# Airbeamv0_01-rn4020.net
KiCad netlist of a schematic drawn in EAGLE
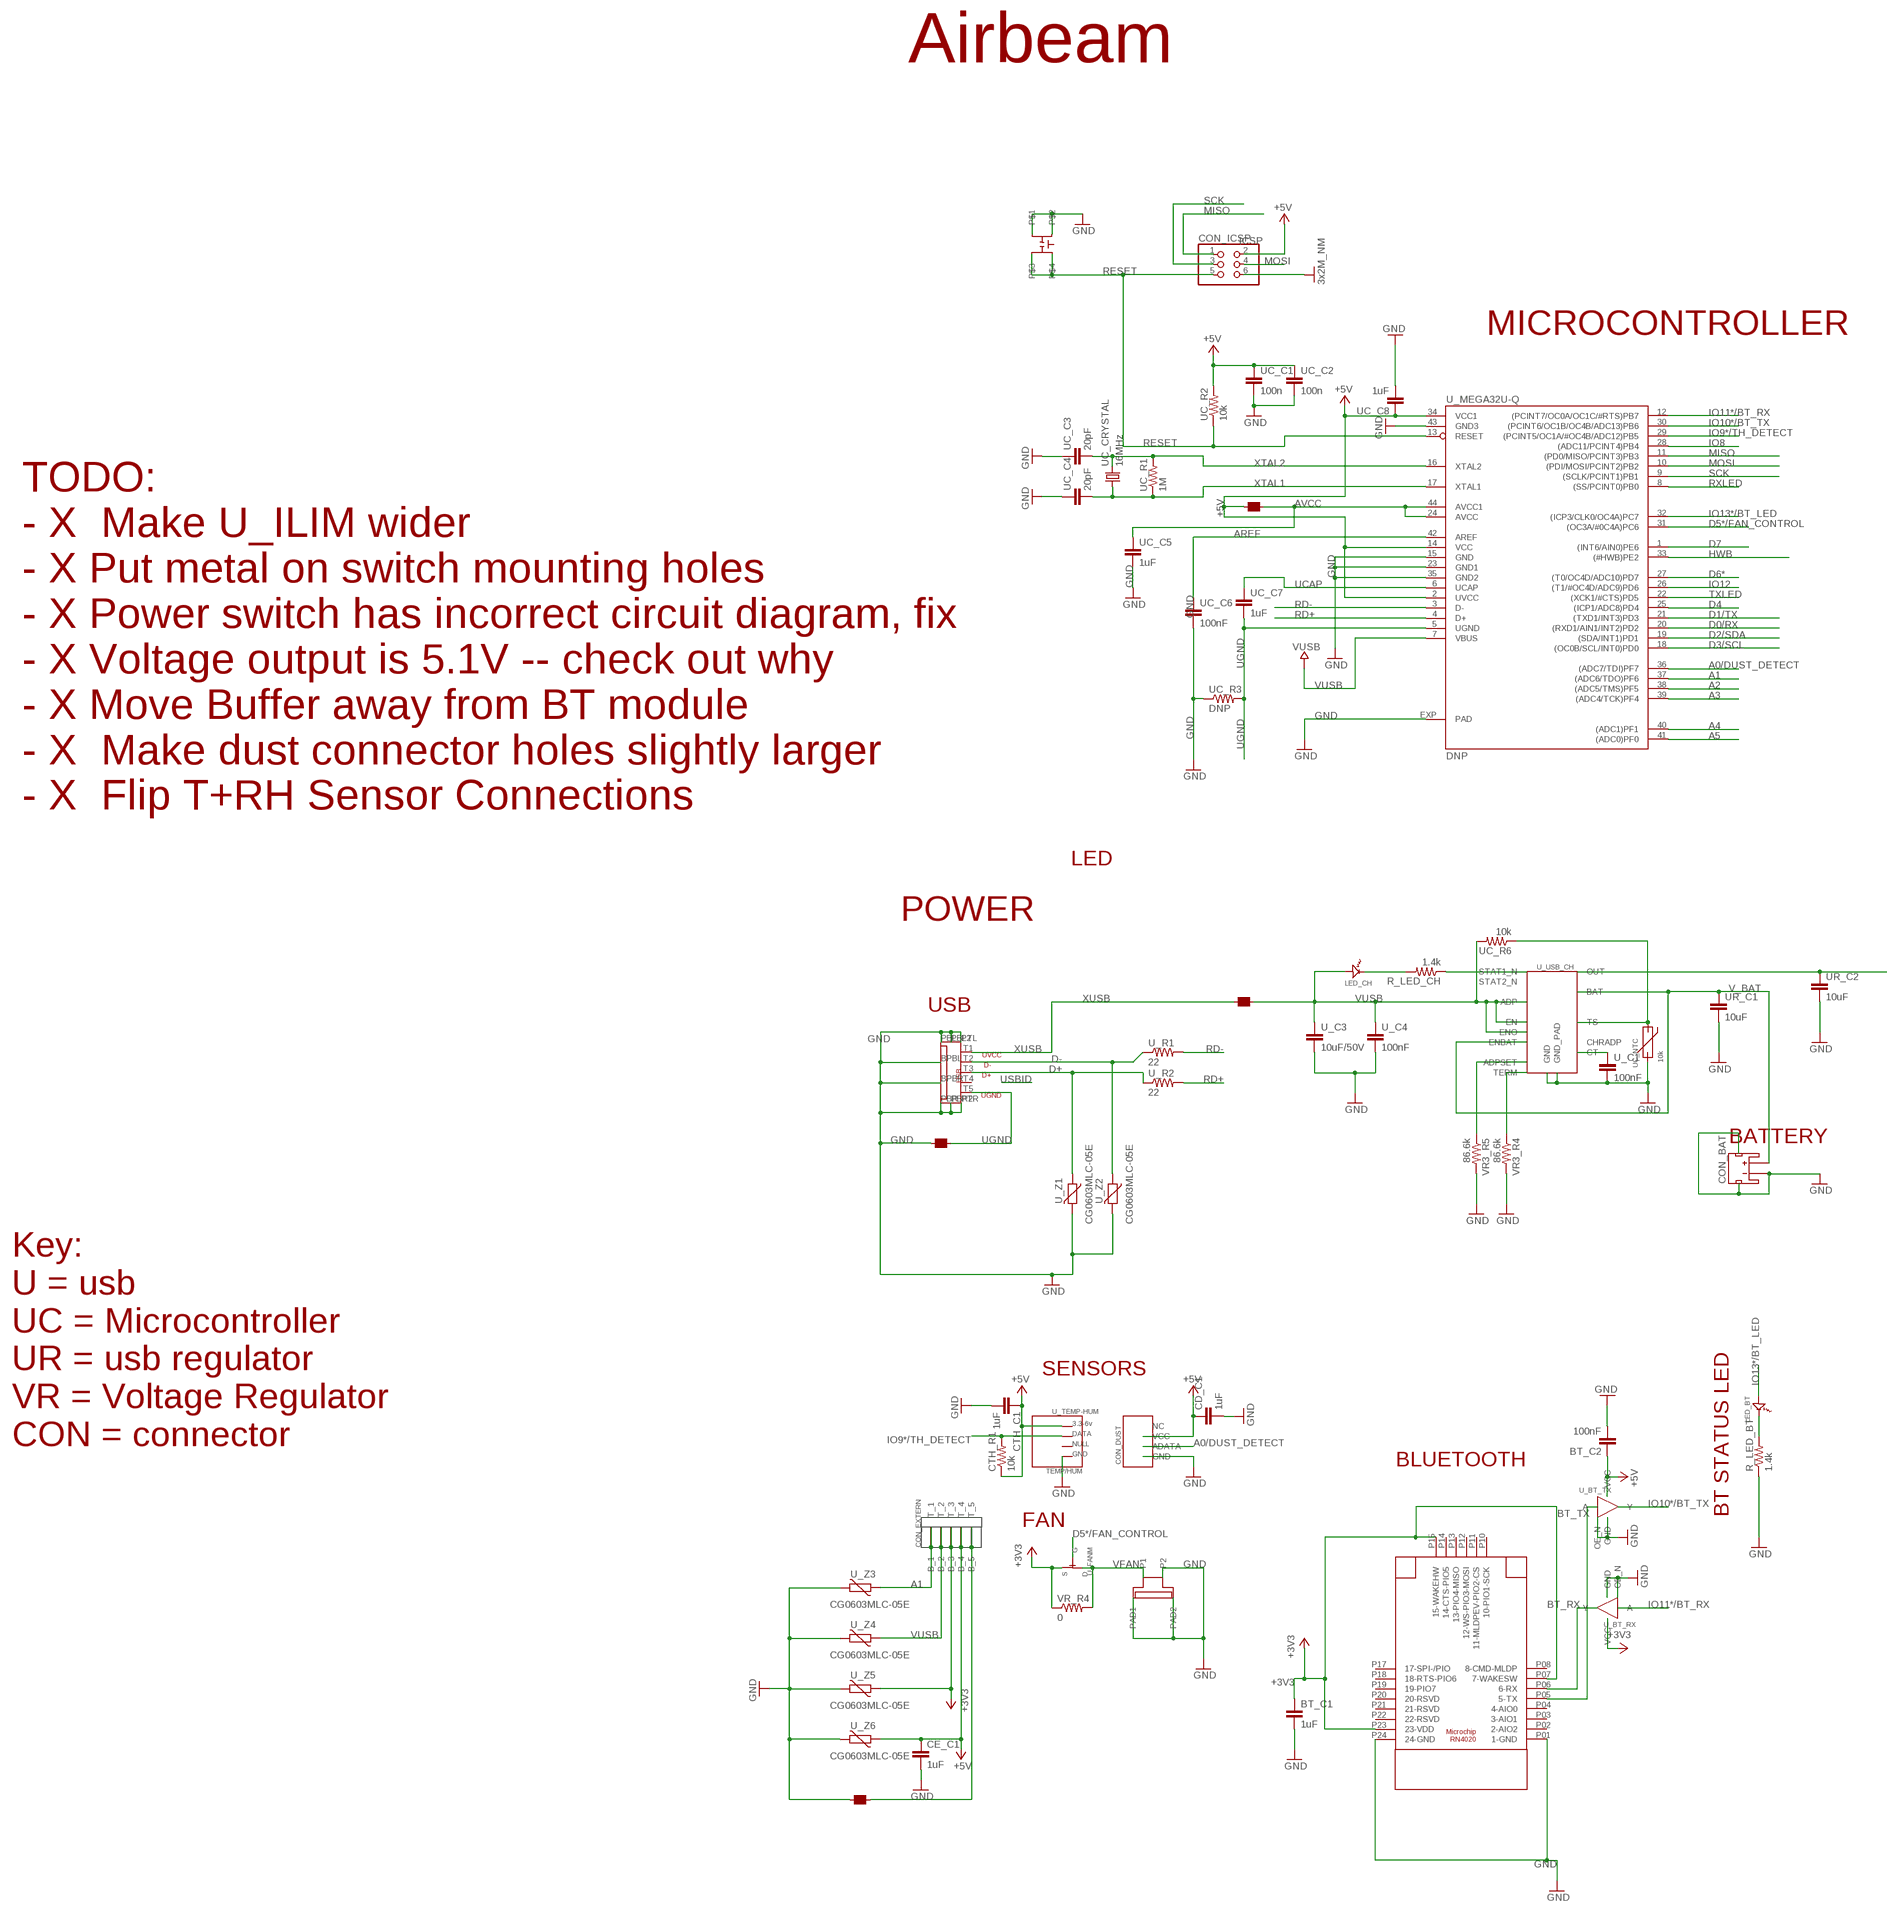
[diagram p0: schematic, sheet 1, part 1 of 2]
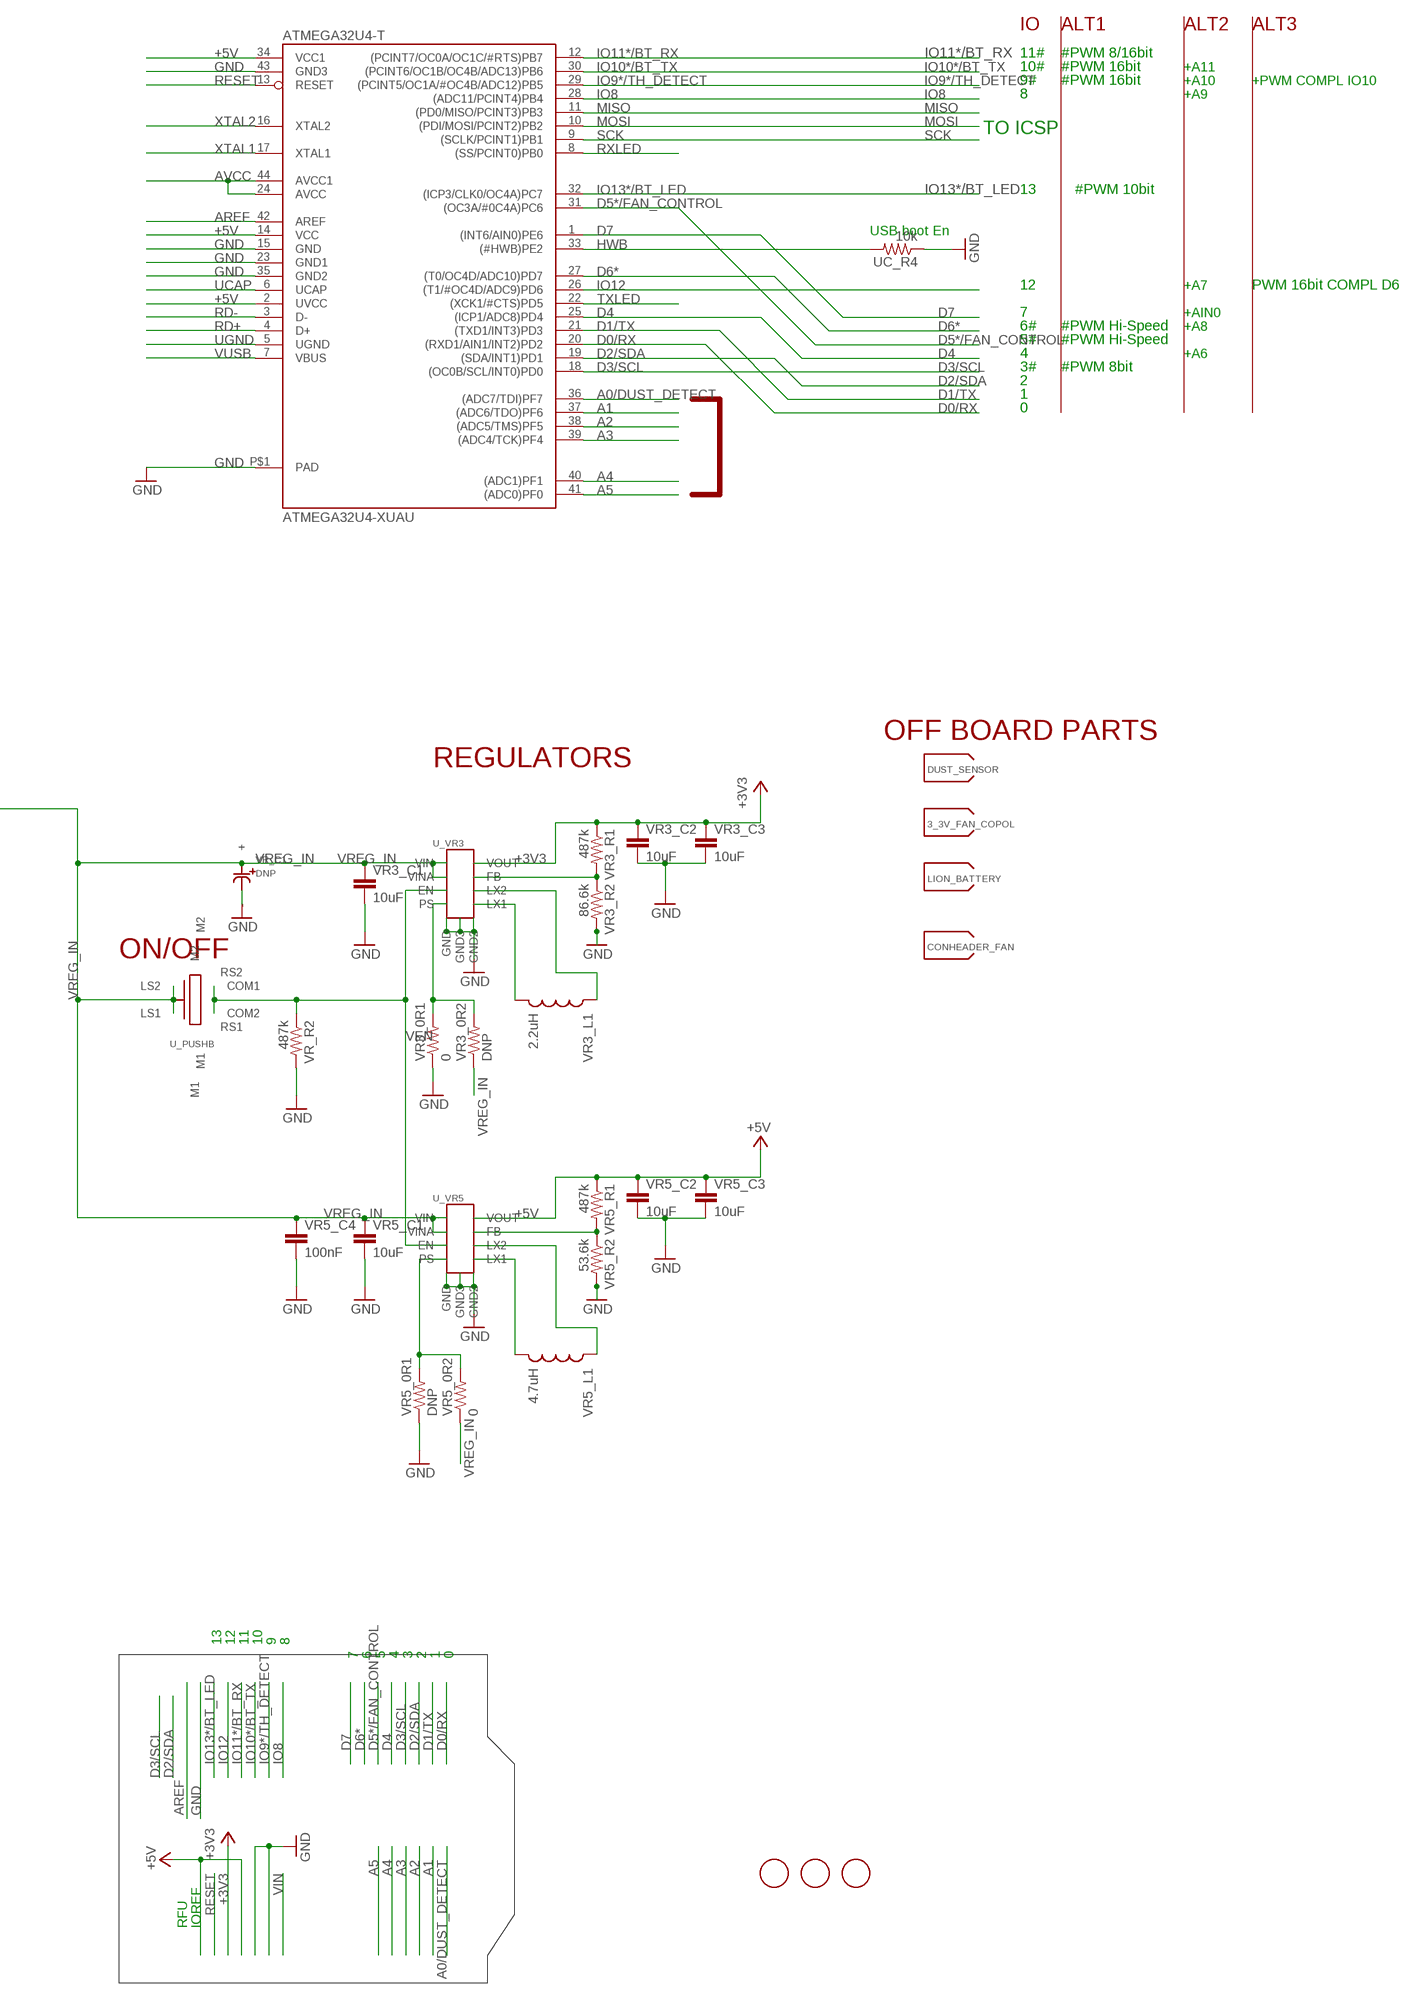
[diagram p1: schematic, sheet 1, part 2 of 2]

(export (version "E")
  (design (tool "Eeschema 10.0.6"))
  (components
    (comp (ref "3_3V_FAN_COPOL")
      (value "OFF_BOARD")
      (footprint "eagle-import:EMPTY")
      (fields (field (name "PARTNO") "F16FB-05LLC/E"))
      (libsource (lib "eagle-import") (part "PART_OFFBOARD"))
    )
    (comp (ref "ATMEGA32U4-T")
      (value "ATMEGA32U4-XUAU")
      (footprint "eagle-import:TQFP44-PAD")
      (fields (field (name "PARTNO") "ATMEGA32U4-AU"))
      (libsource (lib "eagle-import") (part "ATMEGA32U4-XUAU"))
    )
    (comp (ref "BT_C1")
      (value "1uF")
      (footprint "eagle-import:0603-CAP")
      (fields (field (name "PARTNO") "C1608X5R1C105K080AA"))
      (libsource (lib "eagle-import") (part "CAP0603-CAP"))
    )
    (comp (ref "BT_C2")
      (value "100nF")
      (footprint "eagle-import:0603-CAP")
      (fields (field (name "PARTNO") "C1608X7R1E104K080AA"))
      (libsource (lib "eagle-import") (part "CAP0603-CAP"))
    )
    (comp (ref "CA_FB1")
      (value "FERITE_BEAD")
      (footprint "eagle-import:U_FB1")
      (fields (field (name "PARTNO") "MH2029-600Y"))
      (libsource (lib "eagle-import") (part "FERITE_BEAD"))
    )
    (comp (ref "CD_C1")
      (value "1uF")
      (footprint "eagle-import:0603-CAP")
      (fields (field (name "PARTNO") "C1608X5R1C105K080AA"))
      (libsource (lib "eagle-import") (part "CAP0603-CAP"))
    )
    (comp (ref "CE_C1")
      (value "1uF")
      (footprint "eagle-import:0603-CAP")
      (fields (field (name "PARTNO") "C1608X5R1C105K080AA"))
      (libsource (lib "eagle-import") (part "CAP0603-CAP"))
    )
    (comp (ref "CONHEADER_FAN")
      (value "OFF_BOARD")
      (footprint "eagle-import:EMPTY")
      (fields (field (name "PARTNO") "02SUR-32S"))
      (libsource (lib "eagle-import") (part "PART_OFFBOARD"))
    )
    (comp (ref "CON_BAT")
      (value "CON_BAT")
      (footprint "eagle-import:JST-2-SMD")
      (fields (field (name "PARTNO") "S2B-PH-SM4-TB(LF)(SN)"))
      (libsource (lib "eagle-import") (part "JST_2MM_MALE"))
    )
    (comp (ref "CON_DUST")
      (value "CON_DUST")
      (footprint "eagle-import:S4B-EH")
      (fields (field (name "PARTNO") "S4B-EH"))
      (libsource (lib "eagle-import") (part "CON_DUST"))
    )
    (comp (ref "CON_EXTERN")
      (value "TBLOCK_5")
      (footprint "eagle-import:TBLOCK_5")
      (fields (field (name "PARTNO") "1770911"))
      (libsource (lib "eagle-import") (part "TBLOCK_5"))
    )
    (comp (ref "CON_FAN")
      (value "SUR_2PIN")
      (footprint "eagle-import:JST-0.8MM")
      (fields (field (name "PARTNO") "SM02B-SURS-TF"))
      (libsource (lib "eagle-import") (part "SUR_2PIN"))
    )
    (comp (ref "CON_ICSP")
      (value "ICSP")
      (footprint "eagle-import:2X03")
      (fields (field (name "PARTNO") "67997-206HLF "))
      (libsource (lib "eagle-import") (part "PINHD-2X3"))
    )
    (comp (ref "CON_USB")
      (value "USB-FCI")
      (footprint "eagle-import:USB-FCI")
      (fields (field (name "PARTNO") "10103594-0001LF"))
      (libsource (lib "eagle-import") (part "USB-FCI"))
    )
    (comp (ref "CTH_C1")
      (value "1uF")
      (footprint "eagle-import:0603-CAP")
      (fields (field (name "PARTNO") "C1608X5R1C105K080AA"))
      (libsource (lib "eagle-import") (part "CAP0603-CAP"))
    )
    (comp (ref "CTH_R1")
      (value "10k")
      (footprint "eagle-import:0603-RES")
      (fields (field (name "PARTNO") "RC0603JR-0710KL"))
      (libsource (lib "eagle-import") (part "RESISTOR0603-RES"))
    )
    (comp (ref "DUST_SENSOR")
      (value "OFF_BOARD")
      (footprint "eagle-import:EMPTY")
      (fields (field (name "PARTNO") "PPD60PV-T2"))
      (libsource (lib "eagle-import") (part "PART_OFFBOARD"))
    )
    (comp (ref "FID1")
      (value "FIDUCIALMOUNT")
      (footprint "eagle-import:FIDUCIA-MOUNT")
      (fields (field (name "PARTNO") "DNP"))
      (libsource (lib "eagle-import") (part "FIDUCIALMOUNT"))
    )
    (comp (ref "FID2")
      (value "FIDUCIALMOUNT")
      (footprint "eagle-import:FIDUCIA-MOUNT")
      (fields (field (name "PARTNO") "DNP"))
      (libsource (lib "eagle-import") (part "FIDUCIALMOUNT"))
    )
    (comp (ref "FID3")
      (value "FIDUCIALMOUNT")
      (footprint "eagle-import:FIDUCIA-MOUNT")
      (fields (field (name "PARTNO") "DNP"))
      (libsource (lib "eagle-import") (part "FIDUCIALMOUNT"))
    )
    (comp (ref "LED_BT")
      (value "LED")
      (footprint "eagle-import:LED_550")
      (fields (field (name "PARTNO") "550-1107F "))
      (libsource (lib "eagle-import") (part "LED"))
    )
    (comp (ref "LED_CH")
      (value "LED")
      (footprint "eagle-import:LED_550")
      (fields (field (name "PARTNO") "550-1307F"))
      (libsource (lib "eagle-import") (part "LED"))
    )
    (comp (ref "LION_BATTERY")
      (value "OFF_BOARD")
      (footprint "eagle-import:EMPTY")
      (fields (field (name "PARTNO") "585460_2000mAh"))
      (libsource (lib "eagle-import") (part "PART_OFFBOARD"))
    )
    (comp (ref "RESET_SWITCH")
      (value "DNP")
      (footprint "eagle-import:SWITCH_TACTILE")
      (fields (field (name "PARTNO") "TL3315NF250Q"))
      (libsource (lib "eagle-import") (part "SWITCH"))
    )
    (comp (ref "R_LED_BT")
      (value "1.4k")
      (footprint "eagle-import:0603-RES")
      (fields (field (name "PARTNO") "RC0603FR-071K4L"))
      (libsource (lib "eagle-import") (part "RESISTOR0603-RES"))
    )
    (comp (ref "R_LED_CH")
      (value "1.4k")
      (footprint "eagle-import:0603-RES")
      (fields (field (name "PARTNO") "RC0603FR-071K4L"))
      (libsource (lib "eagle-import") (part "RESISTOR0603-RES"))
    )
    (comp (ref "U$1")
      (value "RN4020")
      (footprint "eagle-import:RN4020SMD")
      (libsource (lib "eagle-import") (part "RN4020"))
    )
    (comp (ref "UC_C1")
      (value "100n")
      (footprint "eagle-import:0603-CAP")
      (fields (field (name "PARTNO") "C1608X7R1E104K080AA"))
      (libsource (lib "eagle-import") (part "CAP0603-CAP"))
    )
    (comp (ref "UC_C2")
      (value "100n")
      (footprint "eagle-import:0603-CAP")
      (fields (field (name "PARTNO") "C1608X7R1E104K080AA"))
      (libsource (lib "eagle-import") (part "CAP0603-CAP"))
    )
    (comp (ref "UC_C3")
      (value "20pF")
      (footprint "eagle-import:0603-CAP")
      (fields (field (name "PARTNO") "CL10C200JB8NNNC"))
      (libsource (lib "eagle-import") (part "CAP0603-CAP"))
    )
    (comp (ref "UC_C4")
      (value "20pF")
      (footprint "eagle-import:0603-CAP")
      (fields (field (name "PARTNO") "CL10C200JB8NNNC"))
      (libsource (lib "eagle-import") (part "CAP0603-CAP"))
    )
    (comp (ref "UC_C5")
      (value "1uF")
      (footprint "eagle-import:0603-CAP")
      (fields (field (name "PARTNO") "C1608X5R1C105K080AA"))
      (libsource (lib "eagle-import") (part "CAP0603-CAP"))
    )
    (comp (ref "UC_C6")
      (value "100nF")
      (footprint "eagle-import:0603-CAP")
      (fields (field (name "PARTNO") "C1608X7R1E104K080AA"))
      (libsource (lib "eagle-import") (part "CAP0603-CAP"))
    )
    (comp (ref "UC_C7")
      (value "1uF")
      (footprint "eagle-import:0603-CAP")
      (fields (field (name "PARTNO") "C1608X5R1C105K080AA"))
      (libsource (lib "eagle-import") (part "CAP0603-CAP"))
    )
    (comp (ref "UC_C8")
      (value "1uF")
      (footprint "eagle-import:0603-CAP")
      (fields (field (name "PARTNO") "C1608X5R1C105K080AA"))
      (libsource (lib "eagle-import") (part "CAP0603-CAP"))
    )
    (comp (ref "UC_CRYSTAL")
      (value "16MHz")
      (footprint "eagle-import:HC49UP")
      (fields (field (name "PARTNO") "ECS-160-20-3X-TR "))
      (libsource (lib "eagle-import") (part "CRYSTALSMD"))
    )
    (comp (ref "UC_NTC")
      (value "10k")
      (footprint "eagle-import:0402")
      (fields (field (name "PARTNO") "ERT-J0EM103J ") (field (name "PARTNO_1") "ERT-J0EM103J"))
      (libsource (lib "eagle-import") (part "THERMISTOR0402"))
    )
    (comp (ref "UC_R1")
      (value "1M")
      (footprint "eagle-import:0603-RES")
      (fields (field (name "PARTNO") "RC0603FR-071ML"))
      (libsource (lib "eagle-import") (part "RESISTOR0603-RES"))
    )
    (comp (ref "UC_R2")
      (value "10k")
      (footprint "eagle-import:0603-RES")
      (fields (field (name "PARTNO") "RC0603JR-0710KL"))
      (libsource (lib "eagle-import") (part "RESISTOR0603-RES"))
    )
    (comp (ref "UC_R3")
      (value "DNP")
      (footprint "eagle-import:0603-RES")
      (fields (field (name "PARTNO") "RC0603JR-070RL"))
      (libsource (lib "eagle-import") (part "RESISTOR0603-RES"))
    )
    (comp (ref "UC_R4")
      (value "10k")
      (footprint "eagle-import:0603-RES")
      (fields (field (name "PARTNO") "RC0603JR-0710KL"))
      (libsource (lib "eagle-import") (part "RESISTOR0603-RES"))
    )
    (comp (ref "UC_R6")
      (value "10k")
      (footprint "eagle-import:0603-RES")
      (fields (field (name "PARTNO") "RC0603JR-0710KL"))
      (libsource (lib "eagle-import") (part "RESISTOR0603-RES"))
    )
    (comp (ref "UR_C1")
      (value "10uF")
      (footprint "eagle-import:0805")
      (fields (field (name "PARTNO") "C2012X5R1C106K085AC"))
      (libsource (lib "eagle-import") (part "CAP0805"))
    )
    (comp (ref "UR_C2")
      (value "10uF")
      (footprint "eagle-import:0805")
      (fields (field (name "PARTNO") "C2012X5R1C106K085AC"))
      (libsource (lib "eagle-import") (part "CAP0805"))
    )
    (comp (ref "U_BT_RX")
      (value "V_BUFFER")
      (footprint "eagle-import:SOT23-5")
      (fields (field (name "PARTNO") "SN74LVC1G125DBVR"))
      (libsource (lib "eagle-import") (part "V_BUFFER"))
    )
    (comp (ref "U_BT_TX")
      (value "V_BUFFER")
      (footprint "eagle-import:SOT23-5")
      (fields (field (name "PARTNO") "SN74LVC1G125DBVR"))
      (libsource (lib "eagle-import") (part "V_BUFFER"))
    )
    (comp (ref "U_C1")
      (value "100nF")
      (footprint "eagle-import:0603-CAP")
      (fields (field (name "PARTNO") "C1608X7R1E104K080AA"))
      (libsource (lib "eagle-import") (part "CAP0603-CAP"))
    )
    (comp (ref "U_C3")
      (value "10uF/50V")
      (footprint "eagle-import:1206")
      (fields (field (name "PARTNO") "CL31A106KBHNNNE "))
      (libsource (lib "eagle-import") (part "CAP1206"))
    )
    (comp (ref "U_C4")
      (value "100nF")
      (footprint "eagle-import:0603-CAP")
      (fields (field (name "PARTNO") "CC0603ZRY5V9BB104"))
      (libsource (lib "eagle-import") (part "CAP0603-CAP"))
    )
    (comp (ref "U_FANM")
      (value "DNP")
      (footprint "eagle-import:SOT23")
      (fields (field (name "PARTNO") "NDS331N"))
      (libsource (lib "eagle-import") (part "MOSFET-N"))
    )
    (comp (ref "U_FB1")
      (value "FERITE_BEAD")
      (footprint "eagle-import:U_FB1")
      (fields (field (name "PARTNO") "MH2029-600Y"))
      (libsource (lib "eagle-import") (part "FERITE_BEAD"))
    )
    (comp (ref "U_FB2")
      (value "FERITE_BEAD")
      (footprint "eagle-import:U_FB1")
      (fields (field (name "PARTNO") "MH2029-600Y"))
      (libsource (lib "eagle-import") (part "FERITE_BEAD"))
    )
    (comp (ref "U_FB3")
      (value "FERITE_BEAD")
      (footprint "eagle-import:U_FB1")
      (fields (field (name "PARTNO") "MH2029-600Y"))
      (libsource (lib "eagle-import") (part "FERITE_BEAD"))
    )
    (comp (ref "U_MEGA32U-Q")
      (value "DNP")
      (footprint "eagle-import:QFN44ML7X7")
      (fields (field (name "PARTNO") "ATMEGA32U4-MU "))
      (libsource (lib "eagle-import") (part "ATMEGA32U4-XUMU"))
    )
    (comp (ref "U_PUSHB")
      (value "PUSHBUTTON")
      (footprint "eagle-import:PUSHBUTTON")
      (fields (field (name "PARTNO") "LC2259EENP"))
      (libsource (lib "eagle-import") (part "PUSHBUTTON"))
    )
    (comp (ref "U_R1")
      (value "22")
      (footprint "eagle-import:0603-RES")
      (fields (field (name "PARTNO") "RC0603JR-0722RL"))
      (libsource (lib "eagle-import") (part "RESISTOR0603-RES"))
    )
    (comp (ref "U_R2")
      (value "22")
      (footprint "eagle-import:0603-RES")
      (fields (field (name "PARTNO") "RC0603JR-0722RL"))
      (libsource (lib "eagle-import") (part "RESISTOR0603-RES"))
    )
    (comp (ref "U_TEMP-HUM")
      (value "RHT03")
      (footprint "eagle-import:RHT03")
      (fields (field (name "PARTNO") "RHT03 "))
      (libsource (lib "eagle-import") (part "RHT03"))
    )
    (comp (ref "U_USB_CH")
      (value "USB-BATTERY_LOAD")
      (footprint "eagle-import:TDFN33-14")
      (fields (field (name "PARTNO") "AAT3672IWO-4.2-1-T1") (field (name "PARTNO_1") "AAT3672IWO-4.2-1-T1"))
      (libsource (lib "eagle-import") (part "USB-BATTERY_LOAD"))
    )
    (comp (ref "U_VR3")
      (value "VREG-RTEC6150")
      (footprint "eagle-import:WFDFN-10")
      (fields (field (name "PARTNO") "RT6150BGQW"))
      (libsource (lib "eagle-import") (part "VREG-RTEC6150"))
    )
    (comp (ref "U_VR5")
      (value "VREG-RTEC6150")
      (footprint "eagle-import:WFDFN-10")
      (fields (field (name "PARTNO") "RT6150BGQW"))
      (libsource (lib "eagle-import") (part "VREG-RTEC6150"))
    )
    (comp (ref "U_Z1")
      (value "CG0603MLC-05E")
      (footprint "eagle-import:CT_CN0603")
      (libsource (lib "eagle-import") (part "VARISTORCN0603"))
    )
    (comp (ref "U_Z2")
      (value "CG0603MLC-05E")
      (footprint "eagle-import:CT_CN0603")
      (libsource (lib "eagle-import") (part "VARISTORCN0603"))
    )
    (comp (ref "U_Z3")
      (value "CG0603MLC-05E")
      (footprint "eagle-import:CT_CN0603")
      (libsource (lib "eagle-import") (part "VARISTORCN0603"))
    )
    (comp (ref "U_Z4")
      (value "CG0603MLC-05E")
      (footprint "eagle-import:CT_CN0603")
      (libsource (lib "eagle-import") (part "VARISTORCN0603"))
    )
    (comp (ref "U_Z5")
      (value "CG0603MLC-05E")
      (footprint "eagle-import:CT_CN0603")
      (libsource (lib "eagle-import") (part "VARISTORCN0603"))
    )
    (comp (ref "U_Z6")
      (value "CG0603MLC-05E")
      (footprint "eagle-import:CT_CN0603")
      (libsource (lib "eagle-import") (part "VARISTORCN0603"))
    )
    (comp (ref "VR3_0R1")
      (value "0")
      (footprint "eagle-import:0603-RES")
      (fields (field (name "PARTNO") "RC0603JR-070RL"))
      (libsource (lib "eagle-import") (part "RESISTOR0603-RES"))
    )
    (comp (ref "VR3_0R2")
      (value "DNP")
      (footprint "eagle-import:0603-RES")
      (fields (field (name "PARTNO") "RC0603JR-070RL"))
      (libsource (lib "eagle-import") (part "RESISTOR0603-RES"))
    )
    (comp (ref "VR3_C1")
      (value "10uF")
      (footprint "eagle-import:0805")
      (fields (field (name "PARTNO") "C2012X5R1C106K085AC"))
      (libsource (lib "eagle-import") (part "CAP0805"))
    )
    (comp (ref "VR3_C2")
      (value "10uF")
      (footprint "eagle-import:0805")
      (fields (field (name "PARTNO") "C2012X5R1C106K085AC"))
      (libsource (lib "eagle-import") (part "CAP0805"))
    )
    (comp (ref "VR3_C3")
      (value "10uF")
      (footprint "eagle-import:0805")
      (fields (field (name "PARTNO") "C2012X5R1C106K085AC"))
      (libsource (lib "eagle-import") (part "CAP0805"))
    )
    (comp (ref "VR3_L1")
      (value "2.2uH")
      (footprint "eagle-import:1210")
      (fields (field (name "PARTNO") "BRL3225T2R2M"))
      (libsource (lib "eagle-import") (part "INDUCTOR1210"))
    )
    (comp (ref "VR3_R1")
      (value "487k")
      (footprint "eagle-import:0603-RES")
      (fields (field (name "PARTNO") "ERJ-3EKF4873V"))
      (libsource (lib "eagle-import") (part "RESISTOR0603"))
    )
    (comp (ref "VR3_R2")
      (value "86.6k")
      (footprint "eagle-import:0603-RES")
      (fields (field (name "PARTNO") "ERJ-3EKF8662V"))
      (libsource (lib "eagle-import") (part "RESISTOR0603"))
    )
    (comp (ref "VR3_R4")
      (value "86.6k")
      (footprint "eagle-import:0603-RES")
      (fields (field (name "PARTNO") "ERJ-3EKF8662V"))
      (libsource (lib "eagle-import") (part "RESISTOR0603"))
    )
    (comp (ref "VR3_R5")
      (value "86.6k")
      (footprint "eagle-import:0603-RES")
      (fields (field (name "PARTNO") "ERJ-3EKF8662V"))
      (libsource (lib "eagle-import") (part "RESISTOR0603"))
    )
    (comp (ref "VR5_0R1")
      (value "DNP")
      (footprint "eagle-import:0603-RES")
      (fields (field (name "PARTNO") "RC0603JR-070RL"))
      (libsource (lib "eagle-import") (part "RESISTOR0603-RES"))
    )
    (comp (ref "VR5_0R2")
      (value "0")
      (footprint "eagle-import:0603-RES")
      (fields (field (name "PARTNO") "RC0603JR-070RL"))
      (libsource (lib "eagle-import") (part "RESISTOR0603-RES"))
    )
    (comp (ref "VR5_C1")
      (value "10uF")
      (footprint "eagle-import:0805")
      (fields (field (name "PARTNO") "C2012X5R1C106K085AC"))
      (libsource (lib "eagle-import") (part "CAP0805"))
    )
    (comp (ref "VR5_C2")
      (value "10uF")
      (footprint "eagle-import:0805")
      (fields (field (name "PARTNO") "C2012X5R1C106K085AC"))
      (libsource (lib "eagle-import") (part "CAP0805"))
    )
    (comp (ref "VR5_C3")
      (value "10uF")
      (footprint "eagle-import:0805")
      (fields (field (name "PARTNO") "C2012X5R1C106K085AC"))
      (libsource (lib "eagle-import") (part "CAP0805"))
    )
    (comp (ref "VR5_C4")
      (value "100nF")
      (footprint "eagle-import:0603-CAP")
      (fields (field (name "PARTNO") "C1608X7R1E104K080AA"))
      (libsource (lib "eagle-import") (part "CAP0603-CAP"))
    )
    (comp (ref "VR5_L1")
      (value "4.7uH")
      (footprint "eagle-import:1210")
      (fields (field (name "PARTNO") "CBC3225T4R7MR"))
      (libsource (lib "eagle-import") (part "INDUCTOR1210"))
    )
    (comp (ref "VR5_R1")
      (value "487k")
      (footprint "eagle-import:0603-RES")
      (fields (field (name "PARTNO") "ERJ-3EKF4873V"))
      (libsource (lib "eagle-import") (part "RESISTOR0603"))
    )
    (comp (ref "VR5_R2")
      (value "53.6k")
      (footprint "eagle-import:0603-RES")
      (fields (field (name "PARTNO") "RC0805FR-0753K6L"))
      (libsource (lib "eagle-import") (part "RESISTOR0603"))
    )
    (comp (ref "VR_C1")
      (value "DNP")
      (footprint "eagle-import:2917_CAP")
      (fields (field (name "PARTNO") "T491D107K010AT "))
      (libsource (lib "eagle-import") (part "CAP_POL120UF"))
    )
    (comp (ref "VR_R2")
      (value "487k")
      (footprint "eagle-import:0603-RES")
      (fields (field (name "PARTNO") "ERJ-3EKF4873V"))
      (libsource (lib "eagle-import") (part "RESISTOR0603"))
    )
    (comp (ref "VR_R4")
      (value "0")
      (footprint "eagle-import:0603-RES")
      (fields (field (name "PARTNO") "RC0603JR-070RL"))
      (libsource (lib "eagle-import") (part "RESISTOR0603"))
    )
  )
  (nets
    (net (code "1") (name "+3V3") (class "Default")
      (node (ref "BT_C1") (pin "1") (pinfunction "1_1") (pintype "passive"))
      (node (ref "CON_EXTERN") (pin "B_3") (pinfunction "B_3_B_3") (pintype "bidirectional"))
      (node (ref "CON_EXTERN") (pin "T_3") (pinfunction "T_3_T_3") (pintype "bidirectional"))
      (node (ref "U$1") (pin "P07") (pinfunction "7-WAKESW_P07") (pintype "bidirectional"))
      (node (ref "U$1") (pin "P15") (pinfunction "15-WAKEHW_P15") (pintype "bidirectional"))
      (node (ref "U$1") (pin "P23") (pinfunction "23-VDD_P23") (pintype "bidirectional"))
      (node (ref "U_BT_RX") (pin "5") (pinfunction "VCC_5") (pintype "bidirectional"))
      (node (ref "U_FANM") (pin "2") (pinfunction "P$2_2") (pintype "bidirectional"))
      (node (ref "U_VR3") (pin "P$1") (pinfunction "VOUT_P$1") (pintype "bidirectional"))
      (node (ref "U_Z5") (pin "1") (pinfunction "1_1") (pintype "passive"))
      (node (ref "VR3_C2") (pin "1") (pinfunction "1_1") (pintype "passive"))
      (node (ref "VR3_C3") (pin "1") (pinfunction "1_1") (pintype "passive"))
      (node (ref "VR3_R1") (pin "1") (pinfunction "1_1") (pintype "passive"))
      (node (ref "VR_R4") (pin "1") (pinfunction "1_1") (pintype "passive"))
    )
    (net (code "2") (name "+5V") (class "Default")
      (node (ref "ATMEGA32U4-T") (pin "14") (pinfunction "VCC_14") (pintype "power_in"))
      (node (ref "ATMEGA32U4-T") (pin "2") (pinfunction "UVCC_2") (pintype "power_in"))
      (node (ref "ATMEGA32U4-T") (pin "34") (pinfunction "VCC1_34") (pintype "power_in"))
      (node (ref "BT_C2") (pin "1") (pinfunction "1_1") (pintype "passive"))
      (node (ref "CD_C1") (pin "1") (pinfunction "1_1") (pintype "passive"))
      (node (ref "CE_C1") (pin "1") (pinfunction "1_1") (pintype "passive"))
      (node (ref "CON_DUST") (pin "P$3") (pinfunction "VCC_P$3") (pintype "bidirectional"))
      (node (ref "CON_EXTERN") (pin "B_4") (pinfunction "B_4_B_4") (pintype "bidirectional"))
      (node (ref "CON_EXTERN") (pin "T_4") (pinfunction "T_4_T_4") (pintype "bidirectional"))
      (node (ref "CON_ICSP") (pin "2") (pinfunction "2_2") (pintype "passive"))
      (node (ref "CTH_C1") (pin "1") (pinfunction "1_1") (pintype "passive"))
      (node (ref "CTH_R1") (pin "1") (pinfunction "1_1") (pintype "passive"))
      (node (ref "UC_C1") (pin "1") (pinfunction "1_1") (pintype "passive"))
      (node (ref "UC_C2") (pin "1") (pinfunction "1_1") (pintype "passive"))
      (node (ref "UC_C8") (pin "1") (pinfunction "1_1") (pintype "passive"))
      (node (ref "UC_R2") (pin "2") (pinfunction "2_2") (pintype "passive"))
      (node (ref "U_BT_TX") (pin "5") (pinfunction "VCC_5") (pintype "bidirectional"))
      (node (ref "U_FB2") (pin "P$1") (pinfunction "P$1_P$1") (pintype "passive"))
      (node (ref "U_MEGA32U-Q") (pin "14") (pinfunction "VCC_14") (pintype "power_in"))
      (node (ref "U_MEGA32U-Q") (pin "2") (pinfunction "UVCC_2") (pintype "power_in"))
      (node (ref "U_MEGA32U-Q") (pin "34") (pinfunction "VCC1_34") (pintype "power_in"))
      (node (ref "U_TEMP-HUM") (pin "P$1") (pinfunction "P$1_P$1") (pintype "bidirectional"))
      (node (ref "U_VR5") (pin "P$1") (pinfunction "VOUT_P$1") (pintype "bidirectional"))
      (node (ref "U_Z6") (pin "1") (pinfunction "1_1") (pintype "passive"))
      (node (ref "VR5_C2") (pin "1") (pinfunction "1_1") (pintype "passive"))
      (node (ref "VR5_C3") (pin "1") (pinfunction "1_1") (pintype "passive"))
      (node (ref "VR5_R1") (pin "1") (pinfunction "1_1") (pintype "passive"))
    )
    (net (code "3") (name "/A0{slash}DUST_DETECT") (class "Default")
      (node (ref "ATMEGA32U4-T") (pin "36") (pinfunction "(ADC7/TDI)PF7_36") (pintype "bidirectional"))
      (node (ref "CON_DUST") (pin "P$2") (pinfunction "ADATA_P$2") (pintype "bidirectional"))
      (node (ref "U_MEGA32U-Q") (pin "36") (pinfunction "(ADC7/TDI)PF7_36") (pintype "bidirectional"))
    )
    (net (code "4") (name "/A1") (class "Default")
      (node (ref "ATMEGA32U4-T") (pin "37") (pinfunction "(ADC6/TDO)PF6_37") (pintype "bidirectional"))
      (node (ref "CON_EXTERN") (pin "B_1") (pinfunction "B_1_B_1") (pintype "bidirectional"))
      (node (ref "CON_EXTERN") (pin "T_1") (pinfunction "T_1_T_1") (pintype "bidirectional"))
      (node (ref "U_MEGA32U-Q") (pin "37") (pinfunction "(ADC6/TDO)PF6_37") (pintype "bidirectional"))
      (node (ref "U_Z3") (pin "1") (pinfunction "1_1") (pintype "passive"))
    )
    (net (code "5") (name "/A2") (class "Default")
      (node (ref "ATMEGA32U4-T") (pin "38") (pinfunction "(ADC5/TMS)PF5_38") (pintype "bidirectional"))
      (node (ref "U_MEGA32U-Q") (pin "38") (pinfunction "(ADC5/TMS)PF5_38") (pintype "bidirectional"))
    )
    (net (code "6") (name "/A3") (class "Default")
      (node (ref "ATMEGA32U4-T") (pin "39") (pinfunction "(ADC4/TCK)PF4_39") (pintype "bidirectional"))
      (node (ref "U_MEGA32U-Q") (pin "39") (pinfunction "(ADC4/TCK)PF4_39") (pintype "bidirectional"))
    )
    (net (code "7") (name "/A4") (class "Default")
      (node (ref "ATMEGA32U4-T") (pin "40") (pinfunction "(ADC1)PF1_40") (pintype "bidirectional"))
      (node (ref "U_MEGA32U-Q") (pin "40") (pinfunction "(ADC1)PF1_40") (pintype "bidirectional"))
    )
    (net (code "8") (name "/A5") (class "Default")
      (node (ref "ATMEGA32U4-T") (pin "41") (pinfunction "(ADC0)PF0_41") (pintype "bidirectional"))
      (node (ref "U_MEGA32U-Q") (pin "41") (pinfunction "(ADC0)PF0_41") (pintype "bidirectional"))
    )
    (net (code "9") (name "/AREF") (class "Default")
      (node (ref "ATMEGA32U4-T") (pin "42") (pinfunction "AREF_42") (pintype "power_in"))
      (node (ref "UC_C6") (pin "1") (pinfunction "1_1") (pintype "passive"))
      (node (ref "U_MEGA32U-Q") (pin "42") (pinfunction "AREF_42") (pintype "power_in"))
    )
    (net (code "10") (name "/AVCC") (class "Default")
      (node (ref "ATMEGA32U4-T") (pin "24") (pinfunction "AVCC_24") (pintype "power_in"))
      (node (ref "ATMEGA32U4-T") (pin "44") (pinfunction "AVCC1_44") (pintype "power_in"))
      (node (ref "UC_C5") (pin "1") (pinfunction "1_1") (pintype "passive"))
      (node (ref "U_FB2") (pin "P$2") (pinfunction "P$2_P$2") (pintype "passive"))
      (node (ref "U_MEGA32U-Q") (pin "24") (pinfunction "AVCC_24") (pintype "power_in"))
      (node (ref "U_MEGA32U-Q") (pin "44") (pinfunction "AVCC1_44") (pintype "power_in"))
    )
    (net (code "11") (name "/BT_RX") (class "Default")
      (node (ref "U$1") (pin "P06") (pinfunction "6-RX_P06") (pintype "bidirectional"))
      (node (ref "U_BT_RX") (pin "4") (pinfunction "Y_4") (pintype "bidirectional"))
    )
    (net (code "12") (name "/BT_TX") (class "Default")
      (node (ref "U$1") (pin "P05") (pinfunction "5-TX_P05") (pintype "bidirectional"))
      (node (ref "U_BT_TX") (pin "2") (pinfunction "A_2") (pintype "bidirectional"))
    )
    (net (code "13") (name "/D+") (class "Default")
      (node (ref "CON_USB") (pin "T3") (pinfunction "T3_T3") (pintype "bidirectional"))
      (node (ref "U_R2") (pin "1") (pinfunction "1_1") (pintype "passive"))
      (node (ref "U_Z1") (pin "1") (pinfunction "1_1") (pintype "passive"))
    )
    (net (code "14") (name "/D-") (class "Default")
      (node (ref "CON_USB") (pin "T2") (pinfunction "T2_T2") (pintype "bidirectional"))
      (node (ref "U_R1") (pin "1") (pinfunction "1_1") (pintype "passive"))
      (node (ref "U_Z2") (pin "1") (pinfunction "1_1") (pintype "passive"))
    )
    (net (code "15") (name "/D0{slash}RX") (class "Default")
      (node (ref "ATMEGA32U4-T") (pin "20") (pinfunction "(RXD1/AIN1/INT2)PD2_20") (pintype "bidirectional"))
      (node (ref "U_MEGA32U-Q") (pin "20") (pinfunction "(RXD1/AIN1/INT2)PD2_20") (pintype "bidirectional"))
    )
    (net (code "16") (name "/D1{slash}TX") (class "Default")
      (node (ref "ATMEGA32U4-T") (pin "21") (pinfunction "(TXD1/INT3)PD3_21") (pintype "bidirectional"))
      (node (ref "U_MEGA32U-Q") (pin "21") (pinfunction "(TXD1/INT3)PD3_21") (pintype "bidirectional"))
    )
    (net (code "17") (name "/D2{slash}SDA") (class "Default")
      (node (ref "ATMEGA32U4-T") (pin "19") (pinfunction "(SDA/INT1)PD1_19") (pintype "bidirectional"))
      (node (ref "U_MEGA32U-Q") (pin "19") (pinfunction "(SDA/INT1)PD1_19") (pintype "bidirectional"))
    )
    (net (code "18") (name "/D3{slash}SCL") (class "Default")
      (node (ref "ATMEGA32U4-T") (pin "18") (pinfunction "(OC0B/SCL/INT0)PD0_18") (pintype "bidirectional"))
      (node (ref "U_MEGA32U-Q") (pin "18") (pinfunction "(OC0B/SCL/INT0)PD0_18") (pintype "bidirectional"))
    )
    (net (code "19") (name "/D4") (class "Default")
      (node (ref "ATMEGA32U4-T") (pin "25") (pinfunction "(ICP1/ADC8)PD4_25") (pintype "bidirectional"))
      (node (ref "U_MEGA32U-Q") (pin "25") (pinfunction "(ICP1/ADC8)PD4_25") (pintype "bidirectional"))
    )
    (net (code "20") (name "/D5*{slash}FAN_CONTROL") (class "Default")
      (node (ref "ATMEGA32U4-T") (pin "31") (pinfunction "(OC3A/#0C4A)PC6_31") (pintype "bidirectional"))
      (node (ref "U_FANM") (pin "1") (pinfunction "P$1_1") (pintype "bidirectional"))
      (node (ref "U_MEGA32U-Q") (pin "31") (pinfunction "(OC3A/#0C4A)PC6_31") (pintype "bidirectional"))
    )
    (net (code "21") (name "/D6*") (class "Default")
      (node (ref "ATMEGA32U4-T") (pin "27") (pinfunction "(T0/OC4D/ADC10)PD7_27") (pintype "bidirectional"))
      (node (ref "U_MEGA32U-Q") (pin "27") (pinfunction "(T0/OC4D/ADC10)PD7_27") (pintype "bidirectional"))
    )
    (net (code "22") (name "/D7") (class "Default")
      (node (ref "ATMEGA32U4-T") (pin "1") (pinfunction "(INT6/AIN0)PE6_1") (pintype "bidirectional"))
      (node (ref "U_MEGA32U-Q") (pin "1") (pinfunction "(INT6/AIN0)PE6_1") (pintype "bidirectional"))
    )
    (net (code "23") (name "/HWB") (class "Default")
      (node (ref "ATMEGA32U4-T") (pin "33") (pinfunction "(#HWB)PE2_33") (pintype "bidirectional"))
      (node (ref "UC_R4") (pin "2") (pinfunction "2_2") (pintype "passive"))
      (node (ref "U_MEGA32U-Q") (pin "33") (pinfunction "(#HWB)PE2_33") (pintype "bidirectional"))
    )
    (net (code "24") (name "/IO8") (class "Default")
      (node (ref "ATMEGA32U4-T") (pin "28") (pinfunction "(ADC11/PCINT4)PB4_28") (pintype "bidirectional"))
      (node (ref "U_MEGA32U-Q") (pin "28") (pinfunction "(ADC11/PCINT4)PB4_28") (pintype "bidirectional"))
    )
    (net (code "25") (name "/IO9*{slash}TH_DETECT") (class "Default")
      (node (ref "ATMEGA32U4-T") (pin "29") (pinfunction "(PCINT5/OC1A/#OC4B/ADC12)PB5_29") (pintype "bidirectional"))
      (node (ref "CTH_R1") (pin "2") (pinfunction "2_2") (pintype "passive"))
      (node (ref "U_MEGA32U-Q") (pin "29") (pinfunction "(PCINT5/OC1A/#OC4B/ADC12)PB5_29") (pintype "bidirectional"))
      (node (ref "U_TEMP-HUM") (pin "P$2") (pinfunction "P$2_P$2") (pintype "bidirectional"))
    )
    (net (code "26") (name "/IO10*{slash}BT_TX") (class "Default")
      (node (ref "ATMEGA32U4-T") (pin "30") (pinfunction "(PCINT6/OC1B/OC4B/ADC13)PB6_30") (pintype "bidirectional"))
      (node (ref "U_BT_TX") (pin "4") (pinfunction "Y_4") (pintype "bidirectional"))
      (node (ref "U_MEGA32U-Q") (pin "30") (pinfunction "(PCINT6/OC1B/OC4B/ADC13)PB6_30") (pintype "bidirectional"))
    )
    (net (code "27") (name "/IO11*{slash}BT_RX") (class "Default")
      (node (ref "ATMEGA32U4-T") (pin "12") (pinfunction "(PCINT7/OC0A/OC1C/#RTS)PB7_12") (pintype "bidirectional"))
      (node (ref "U_BT_RX") (pin "2") (pinfunction "A_2") (pintype "bidirectional"))
      (node (ref "U_MEGA32U-Q") (pin "12") (pinfunction "(PCINT7/OC0A/OC1C/#RTS)PB7_12") (pintype "bidirectional"))
    )
    (net (code "28") (name "/IO12") (class "Default")
      (node (ref "ATMEGA32U4-T") (pin "26") (pinfunction "(T1/#OC4D/ADC9)PD6_26") (pintype "bidirectional"))
      (node (ref "U_MEGA32U-Q") (pin "26") (pinfunction "(T1/#OC4D/ADC9)PD6_26") (pintype "bidirectional"))
    )
    (net (code "29") (name "/IO13*{slash}BT_LED") (class "Default")
      (node (ref "ATMEGA32U4-T") (pin "32") (pinfunction "(ICP3/CLK0/OC4A)PC7_32") (pintype "bidirectional"))
      (node (ref "LED_BT") (pin "ANODE") (pinfunction "AN_ANODE") (pintype "bidirectional"))
      (node (ref "U_MEGA32U-Q") (pin "32") (pinfunction "(ICP3/CLK0/OC4A)PC7_32") (pintype "bidirectional"))
    )
    (net (code "30") (name "/MISO") (class "Default")
      (node (ref "ATMEGA32U4-T") (pin "11") (pinfunction "(PD0/MISO/PCINT3)PB3_11") (pintype "bidirectional"))
      (node (ref "CON_ICSP") (pin "1") (pinfunction "1_1") (pintype "passive"))
      (node (ref "U_MEGA32U-Q") (pin "11") (pinfunction "(PD0/MISO/PCINT3)PB3_11") (pintype "bidirectional"))
    )
    (net (code "31") (name "/MOSI") (class "Default")
      (node (ref "ATMEGA32U4-T") (pin "10") (pinfunction "(PDI/MOSI/PCINT2)PB2_10") (pintype "bidirectional"))
      (node (ref "CON_ICSP") (pin "4") (pinfunction "4_4") (pintype "passive"))
      (node (ref "U_MEGA32U-Q") (pin "10") (pinfunction "(PDI/MOSI/PCINT2)PB2_10") (pintype "bidirectional"))
    )
    (net (code "32") (name "/RD+") (class "Default")
      (node (ref "ATMEGA32U4-T") (pin "4") (pinfunction "D+_4") (pintype "bidirectional"))
      (node (ref "U_MEGA32U-Q") (pin "4") (pinfunction "D+_4") (pintype "bidirectional"))
      (node (ref "U_R2") (pin "2") (pinfunction "2_2") (pintype "passive"))
    )
    (net (code "33") (name "/RD-") (class "Default")
      (node (ref "ATMEGA32U4-T") (pin "3") (pinfunction "D-_3") (pintype "bidirectional"))
      (node (ref "U_MEGA32U-Q") (pin "3") (pinfunction "D-_3") (pintype "bidirectional"))
      (node (ref "U_R1") (pin "2") (pinfunction "2_2") (pintype "passive"))
    )
    (net (code "34") (name "/RESET") (class "Default")
      (node (ref "ATMEGA32U4-T") (pin "13") (pinfunction "RESET_13") (pintype "input"))
      (node (ref "CON_ICSP") (pin "5") (pinfunction "5_5") (pintype "passive"))
      (node (ref "RESET_SWITCH") (pin "P3") (pinfunction "P$3_P3") (pintype "bidirectional"))
      (node (ref "RESET_SWITCH") (pin "P4") (pinfunction "P$4_P4") (pintype "bidirectional"))
      (node (ref "UC_R2") (pin "1") (pinfunction "1_1") (pintype "passive"))
      (node (ref "U_MEGA32U-Q") (pin "13") (pinfunction "RESET_13") (pintype "input"))
    )
    (net (code "35") (name "/RXLED") (class "Default")
      (node (ref "ATMEGA32U4-T") (pin "8") (pinfunction "(SS/PCINT0)PB0_8") (pintype "bidirectional"))
      (node (ref "U_MEGA32U-Q") (pin "8") (pinfunction "(SS/PCINT0)PB0_8") (pintype "bidirectional"))
    )
    (net (code "36") (name "/SCK") (class "Default")
      (node (ref "ATMEGA32U4-T") (pin "9") (pinfunction "(SCLK/PCINT1)PB1_9") (pintype "bidirectional"))
      (node (ref "CON_ICSP") (pin "3") (pinfunction "3_3") (pintype "passive"))
      (node (ref "U_MEGA32U-Q") (pin "9") (pinfunction "(SCLK/PCINT1)PB1_9") (pintype "bidirectional"))
    )
    (net (code "37") (name "/TXLED") (class "Default")
      (node (ref "ATMEGA32U4-T") (pin "22") (pinfunction "(XCK1/#CTS)PD5_22") (pintype "bidirectional"))
      (node (ref "U_MEGA32U-Q") (pin "22") (pinfunction "(XCK1/#CTS)PD5_22") (pintype "bidirectional"))
    )
    (net (code "38") (name "/UCAP") (class "Default")
      (node (ref "ATMEGA32U4-T") (pin "6") (pinfunction "UCAP_6") (pintype "passive"))
      (node (ref "UC_C7") (pin "1") (pinfunction "1_1") (pintype "passive"))
      (node (ref "U_MEGA32U-Q") (pin "6") (pinfunction "UCAP_6") (pintype "passive"))
    )
    (net (code "39") (name "/UGND") (class "Default")
      (node (ref "ATMEGA32U4-T") (pin "5") (pinfunction "UGND_5") (pintype "power_in"))
      (node (ref "CON_USB") (pin "T5") (pinfunction "T5_T5") (pintype "bidirectional"))
      (node (ref "UC_C7") (pin "2") (pinfunction "2_2") (pintype "passive"))
      (node (ref "UC_R3") (pin "2") (pinfunction "2_2") (pintype "passive"))
      (node (ref "U_FB1") (pin "P$2") (pinfunction "P$2_P$2") (pintype "passive"))
      (node (ref "U_MEGA32U-Q") (pin "5") (pinfunction "UGND_5") (pintype "power_in"))
    )
    (net (code "41") (name "/VEN") (class "Default")
      (node (ref "U_PUSHB") (pin "C1") (pinfunction "COM1_C1") (pintype "bidirectional"))
      (node (ref "U_PUSHB") (pin "C2") (pinfunction "COM2_C2") (pintype "bidirectional"))
      (node (ref "U_VR3") (pin "P$6") (pinfunction "EN_P$6") (pintype "bidirectional"))
      (node (ref "U_VR5") (pin "P$6") (pinfunction "EN_P$6") (pintype "bidirectional"))
      (node (ref "VR_R2") (pin "1") (pinfunction "1_1") (pintype "passive"))
    )
    (net (code "42") (name "/VFAN") (class "Default")
      (node (ref "CON_FAN") (pin "P1") (pinfunction "P1_P1") (pintype "bidirectional"))
      (node (ref "U_FANM") (pin "3") (pinfunction "P$3_3") (pintype "bidirectional"))
      (node (ref "VR_R4") (pin "2") (pinfunction "2_2") (pintype "passive"))
    )
    (net (code "44") (name "/VREG_IN") (class "Default")
      (node (ref "UR_C2") (pin "1") (pinfunction "1_1") (pintype "passive"))
      (node (ref "U_PUSHB") (pin "LS1") (pinfunction "LS1_LS1") (pintype "bidirectional"))
      (node (ref "U_PUSHB") (pin "LS2") (pinfunction "LS2_LS2") (pintype "bidirectional"))
      (node (ref "U_USB_CH") (pin "P$13") (pinfunction "OUT_P$13") (pintype "bidirectional"))
      (node (ref "U_VR3") (pin "P$5") (pinfunction "VIN_P$5") (pintype "bidirectional"))
      (node (ref "U_VR3") (pin "P$8") (pinfunction "VINA_P$8") (pintype "bidirectional"))
      (node (ref "U_VR5") (pin "P$5") (pinfunction "VIN_P$5") (pintype "bidirectional"))
      (node (ref "U_VR5") (pin "P$8") (pinfunction "VINA_P$8") (pintype "bidirectional"))
      (node (ref "VR3_0R2") (pin "1") (pinfunction "1_1") (pintype "passive"))
      (node (ref "VR3_C1") (pin "1") (pinfunction "1_1") (pintype "passive"))
      (node (ref "VR5_0R2") (pin "1") (pinfunction "1_1") (pintype "passive"))
      (node (ref "VR5_C1") (pin "1") (pinfunction "1_1") (pintype "passive"))
      (node (ref "VR5_C4") (pin "1") (pinfunction "1_1") (pintype "passive"))
      (node (ref "VR_C1") (pin "T+") (pinfunction "+_T+") (pintype "bidirectional"))
    )
    (net (code "45") (name "/V_BAT") (class "Default")
      (node (ref "CON_BAT") (pin "2") (pinfunction "+_2") (pintype "bidirectional"))
      (node (ref "UR_C1") (pin "1") (pinfunction "1_1") (pintype "passive"))
      (node (ref "U_USB_CH") (pin "P$12") (pinfunction "BAT_P$12") (pintype "bidirectional"))
      (node (ref "U_USB_CH") (pin "P$8") (pinfunction "ENBAT_P$8") (pintype "bidirectional"))
    )
    (net (code "46") (name "/XTAL1") (class "Default")
      (node (ref "ATMEGA32U4-T") (pin "17") (pinfunction "XTAL1_17") (pintype "bidirectional"))
      (node (ref "UC_C4") (pin "2") (pinfunction "2_2") (pintype "passive"))
      (node (ref "UC_CRYSTAL") (pin "1") (pinfunction "1_1") (pintype "passive"))
      (node (ref "UC_R1") (pin "1") (pinfunction "1_1") (pintype "passive"))
      (node (ref "U_MEGA32U-Q") (pin "17") (pinfunction "XTAL1_17") (pintype "bidirectional"))
    )
    (net (code "47") (name "/XTAL2") (class "Default")
      (node (ref "ATMEGA32U4-T") (pin "16") (pinfunction "XTAL2_16") (pintype "bidirectional"))
      (node (ref "UC_C3") (pin "2") (pinfunction "2_2") (pintype "passive"))
      (node (ref "UC_CRYSTAL") (pin "2") (pinfunction "2_2") (pintype "passive"))
      (node (ref "UC_R1") (pin "2") (pinfunction "2_2") (pintype "passive"))
      (node (ref "U_MEGA32U-Q") (pin "16") (pinfunction "XTAL2_16") (pintype "bidirectional"))
    )
    (net (code "48") (name "/XUSB") (class "Default")
      (node (ref "CON_USB") (pin "T1") (pinfunction "T1_T1") (pintype "bidirectional"))
      (node (ref "U_FB3") (pin "P$1") (pinfunction "P$1_P$1") (pintype "passive"))
    )
    (net (code "49") (name "3x2M_NM") (class "Default")
      (node (ref "ATMEGA32U4-T") (pin "15") (pinfunction "GND_15") (pintype "power_in"))
      (node (ref "ATMEGA32U4-T") (pin "23") (pinfunction "GND1_23") (pintype "power_in"))
      (node (ref "ATMEGA32U4-T") (pin "35") (pinfunction "GND2_35") (pintype "power_in"))
      (node (ref "ATMEGA32U4-T") (pin "43") (pinfunction "GND3_43") (pintype "power_in"))
      (node (ref "ATMEGA32U4-T") (pin "P$1") (pinfunction "PAD_P$1") (pintype "power_in"))
      (node (ref "BT_C1") (pin "2") (pinfunction "2_2") (pintype "passive"))
      (node (ref "BT_C2") (pin "2") (pinfunction "2_2") (pintype "passive"))
      (node (ref "CA_FB1") (pin "P$1") (pinfunction "P$1_P$1") (pintype "passive"))
      (node (ref "CD_C1") (pin "2") (pinfunction "2_2") (pintype "passive"))
      (node (ref "CE_C1") (pin "2") (pinfunction "2_2") (pintype "passive"))
      (node (ref "CON_BAT") (pin "1") (pinfunction "-_1") (pintype "bidirectional"))
      (node (ref "CON_BAT") (pin "NC1") (pinfunction "PAD1_NC1") (pintype "bidirectional"))
      (node (ref "CON_BAT") (pin "NC2") (pinfunction "PAD2_NC2") (pintype "bidirectional"))
      (node (ref "CON_DUST") (pin "P$1") (pinfunction "GND_P$1") (pintype "bidirectional"))
      (node (ref "CON_FAN") (pin "P2") (pinfunction "P2_P2") (pintype "bidirectional"))
      (node (ref "CON_FAN") (pin "PAD1") (pinfunction "PAD1_PAD1") (pintype "bidirectional"))
      (node (ref "CON_FAN") (pin "PAD2") (pinfunction "PAD2_PAD2") (pintype "bidirectional"))
      (node (ref "CON_ICSP") (pin "6") (pinfunction "6_6") (pintype "passive"))
      (node (ref "CON_USB") (pin "BPBL") (pinfunction "BPBL_BPBL") (pintype "bidirectional"))
      (node (ref "CON_USB") (pin "BPBR") (pinfunction "BPBR_BPBR") (pintype "bidirectional"))
      (node (ref "CON_USB") (pin "PBL") (pinfunction "PBL_PBL") (pintype "bidirectional"))
      (node (ref "CON_USB") (pin "PBL2") (pinfunction "PBL2_PBL2") (pintype "bidirectional"))
      (node (ref "CON_USB") (pin "PBR") (pinfunction "PBR_PBR") (pintype "bidirectional"))
      (node (ref "CON_USB") (pin "PBR2") (pinfunction "PBR2_PBR2") (pintype "bidirectional"))
      (node (ref "CON_USB") (pin "PTL") (pinfunction "PTL_PTL") (pintype "bidirectional"))
      (node (ref "CON_USB") (pin "PTR") (pinfunction "PTR_PTR") (pintype "bidirectional"))
      (node (ref "CTH_C1") (pin "2") (pinfunction "2_2") (pintype "passive"))
      (node (ref "RESET_SWITCH") (pin "P1") (pinfunction "P$1_P1") (pintype "bidirectional"))
      (node (ref "RESET_SWITCH") (pin "P2") (pinfunction "P$2_P2") (pintype "bidirectional"))
      (node (ref "R_LED_BT") (pin "1") (pinfunction "1_1") (pintype "passive"))
      (node (ref "U$1") (pin "P01") (pinfunction "1-GND_P01") (pintype "bidirectional"))
      (node (ref "U$1") (pin "P24") (pinfunction "24-GND_P24") (pintype "bidirectional"))
      (node (ref "UC_C1") (pin "2") (pinfunction "2_2") (pintype "passive"))
      (node (ref "UC_C2") (pin "2") (pinfunction "2_2") (pintype "passive"))
      (node (ref "UC_C3") (pin "1") (pinfunction "1_1") (pintype "passive"))
      (node (ref "UC_C4") (pin "1") (pinfunction "1_1") (pintype "passive"))
      (node (ref "UC_C5") (pin "2") (pinfunction "2_2") (pintype "passive"))
      (node (ref "UC_C6") (pin "2") (pinfunction "2_2") (pintype "passive"))
      (node (ref "UC_C8") (pin "2") (pinfunction "2_2") (pintype "passive"))
      (node (ref "UC_NTC") (pin "1") (pinfunction "P$1_1") (pintype "bidirectional"))
      (node (ref "UC_R3") (pin "1") (pinfunction "1_1") (pintype "passive"))
      (node (ref "UC_R4") (pin "1") (pinfunction "1_1") (pintype "passive"))
      (node (ref "UR_C1") (pin "2") (pinfunction "2_2") (pintype "passive"))
      (node (ref "UR_C2") (pin "2") (pinfunction "2_2") (pintype "passive"))
      (node (ref "U_BT_RX") (pin "1") (pinfunction "OE_N_1") (pintype "bidirectional"))
      (node (ref "U_BT_RX") (pin "3") (pinfunction "GND_3") (pintype "bidirectional"))
      (node (ref "U_BT_TX") (pin "1") (pinfunction "OE_N_1") (pintype "bidirectional"))
      (node (ref "U_BT_TX") (pin "3") (pinfunction "GND_3") (pintype "bidirectional"))
      (node (ref "U_C1") (pin "2") (pinfunction "2_2") (pintype "passive"))
      (node (ref "U_C3") (pin "2") (pinfunction "2_2") (pintype "passive"))
      (node (ref "U_C4") (pin "2") (pinfunction "2_2") (pintype "passive"))
      (node (ref "U_FB1") (pin "P$1") (pinfunction "P$1_P$1") (pintype "passive"))
      (node (ref "U_MEGA32U-Q") (pin "15") (pinfunction "GND_15") (pintype "power_in"))
      (node (ref "U_MEGA32U-Q") (pin "23") (pinfunction "GND1_23") (pintype "power_in"))
      (node (ref "U_MEGA32U-Q") (pin "35") (pinfunction "GND2_35") (pintype "power_in"))
      (node (ref "U_MEGA32U-Q") (pin "43") (pinfunction "GND3_43") (pintype "power_in"))
      (node (ref "U_MEGA32U-Q") (pin "EXP") (pinfunction "PAD_EXP") (pintype "power_in"))
      (node (ref "U_TEMP-HUM") (pin "P$4") (pinfunction "P$4_P$4") (pintype "bidirectional"))
      (node (ref "U_USB_CH") (pin "GND_PAD") (pinfunction "GND_PAD_GND_PAD") (pintype "bidirectional"))
      (node (ref "U_USB_CH") (pin "P$4") (pinfunction "GND_P$4") (pintype "bidirectional"))
      (node (ref "U_VR3") (pin "MID_PAD") (pinfunction "GND3_MID_PAD") (pintype "bidirectional"))
      (node (ref "U_VR3") (pin "P$3") (pinfunction "GND_P$3") (pintype "bidirectional"))
      (node (ref "U_VR3") (pin "P$9") (pinfunction "GND2_P$9") (pintype "bidirectional"))
      (node (ref "U_VR5") (pin "MID_PAD") (pinfunction "GND3_MID_PAD") (pintype "bidirectional"))
      (node (ref "U_VR5") (pin "P$3") (pinfunction "GND_P$3") (pintype "bidirectional"))
      (node (ref "U_VR5") (pin "P$9") (pinfunction "GND2_P$9") (pintype "bidirectional"))
      (node (ref "U_Z1") (pin "2") (pinfunction "2_2") (pintype "passive"))
      (node (ref "U_Z2") (pin "2") (pinfunction "2_2") (pintype "passive"))
      (node (ref "U_Z3") (pin "2") (pinfunction "2_2") (pintype "passive"))
      (node (ref "U_Z4") (pin "2") (pinfunction "2_2") (pintype "passive"))
      (node (ref "U_Z5") (pin "2") (pinfunction "2_2") (pintype "passive"))
      (node (ref "U_Z6") (pin "2") (pinfunction "2_2") (pintype "passive"))
      (node (ref "VR3_0R1") (pin "1") (pinfunction "1_1") (pintype "passive"))
      (node (ref "VR3_C1") (pin "2") (pinfunction "2_2") (pintype "passive"))
      (node (ref "VR3_C2") (pin "2") (pinfunction "2_2") (pintype "passive"))
      (node (ref "VR3_C3") (pin "2") (pinfunction "2_2") (pintype "passive"))
      (node (ref "VR3_R2") (pin "2") (pinfunction "2_2") (pintype "passive"))
      (node (ref "VR3_R4") (pin "2") (pinfunction "2_2") (pintype "passive"))
      (node (ref "VR3_R5") (pin "2") (pinfunction "2_2") (pintype "passive"))
      (node (ref "VR5_0R1") (pin "1") (pinfunction "1_1") (pintype "passive"))
      (node (ref "VR5_C1") (pin "2") (pinfunction "2_2") (pintype "passive"))
      (node (ref "VR5_C2") (pin "2") (pinfunction "2_2") (pintype "passive"))
      (node (ref "VR5_C3") (pin "2") (pinfunction "2_2") (pintype "passive"))
      (node (ref "VR5_C4") (pin "2") (pinfunction "2_2") (pintype "passive"))
      (node (ref "VR5_R2") (pin "2") (pinfunction "2_2") (pintype "passive"))
      (node (ref "VR_C1") (pin "T-") (pinfunction "-_T-") (pintype "bidirectional"))
      (node (ref "VR_R2") (pin "2") (pinfunction "2_2") (pintype "passive"))
    )
    (net (code "50") (name "Net-(CA_FB1-PadP$2)") (class "Default")
      (node (ref "CA_FB1") (pin "P$2") (pinfunction "P$2_P$2") (pintype "passive"))
      (node (ref "CON_EXTERN") (pin "B_5") (pinfunction "B_5_B_5") (pintype "bidirectional"))
      (node (ref "CON_EXTERN") (pin "T_5") (pinfunction "T_5_T_5") (pintype "bidirectional"))
    )
    (net (code "51") (name "Net-(LED_BT-CATH)") (class "Default")
      (node (ref "LED_BT") (pin "CATHODE") (pinfunction "CATH_CATHODE") (pintype "bidirectional"))
      (node (ref "R_LED_BT") (pin "2") (pinfunction "2_2") (pintype "passive"))
    )
    (net (code "52") (name "Net-(LED_CH-CATH)") (class "Default")
      (node (ref "LED_CH") (pin "CATHODE") (pinfunction "CATH_CATHODE") (pintype "bidirectional"))
      (node (ref "R_LED_CH") (pin "2") (pinfunction "2_2") (pintype "passive"))
    )
    (net (code "53") (name "Net-(UC_NTC-P$2)") (class "Default")
      (node (ref "UC_NTC") (pin "2") (pinfunction "P$2_2") (pintype "bidirectional"))
      (node (ref "UC_R6") (pin "1") (pinfunction "1_1") (pintype "passive"))
      (node (ref "U_USB_CH") (pin "P$11") (pinfunction "TS_P$11") (pintype "bidirectional"))
    )
    (net (code "54") (name "Net-(U_USB_CH-ADPSET)") (class "Default")
      (node (ref "U_USB_CH") (pin "P$1") (pinfunction "ADPSET_P$1") (pintype "bidirectional"))
      (node (ref "VR3_R5") (pin "1") (pinfunction "1_1") (pintype "passive"))
    )
    (net (code "55") (name "Net-(U_USB_CH-CT)") (class "Default")
      (node (ref "U_C1") (pin "1") (pinfunction "1_1") (pintype "passive"))
      (node (ref "U_USB_CH") (pin "P$14") (pinfunction "CT_P$14") (pintype "bidirectional"))
    )
    (net (code "56") (name "Net-(U_USB_CH-STAT1_N)") (class "Default")
      (node (ref "R_LED_CH") (pin "1") (pinfunction "1_1") (pintype "passive"))
      (node (ref "U_USB_CH") (pin "P$3") (pinfunction "STAT1_N_P$3") (pintype "bidirectional"))
    )
    (net (code "57") (name "Net-(U_USB_CH-TERM)") (class "Default")
      (node (ref "U_USB_CH") (pin "P$10") (pinfunction "TERM_P$10") (pintype "bidirectional"))
      (node (ref "VR3_R4") (pin "1") (pinfunction "1_1") (pintype "passive"))
    )
    (net (code "58") (name "Net-(U_VR3-FB)") (class "Default")
      (node (ref "U_VR3") (pin "P$10") (pinfunction "FB_P$10") (pintype "bidirectional"))
      (node (ref "VR3_R1") (pin "2") (pinfunction "2_2") (pintype "passive"))
      (node (ref "VR3_R2") (pin "1") (pinfunction "1_1") (pintype "passive"))
    )
    (net (code "59") (name "Net-(U_VR3-LX1)") (class "Default")
      (node (ref "U_VR3") (pin "P$4") (pinfunction "LX1_P$4") (pintype "bidirectional"))
      (node (ref "VR3_L1") (pin "2") (pinfunction "2_2") (pintype "passive"))
    )
    (net (code "60") (name "Net-(U_VR3-LX2)") (class "Default")
      (node (ref "U_VR3") (pin "P$2") (pinfunction "LX2_P$2") (pintype "bidirectional"))
      (node (ref "VR3_L1") (pin "1") (pinfunction "1_1") (pintype "passive"))
    )
    (net (code "61") (name "Net-(U_VR3-PS)") (class "Default")
      (node (ref "U_VR3") (pin "P$7") (pinfunction "PS_P$7") (pintype "bidirectional"))
      (node (ref "VR3_0R1") (pin "2") (pinfunction "2_2") (pintype "passive"))
      (node (ref "VR3_0R2") (pin "2") (pinfunction "2_2") (pintype "passive"))
    )
    (net (code "62") (name "Net-(U_VR5-FB)") (class "Default")
      (node (ref "U_VR5") (pin "P$10") (pinfunction "FB_P$10") (pintype "bidirectional"))
      (node (ref "VR5_R1") (pin "2") (pinfunction "2_2") (pintype "passive"))
      (node (ref "VR5_R2") (pin "1") (pinfunction "1_1") (pintype "passive"))
    )
    (net (code "63") (name "Net-(U_VR5-LX1)") (class "Default")
      (node (ref "U_VR5") (pin "P$4") (pinfunction "LX1_P$4") (pintype "bidirectional"))
      (node (ref "VR5_L1") (pin "2") (pinfunction "2_2") (pintype "passive"))
    )
    (net (code "64") (name "Net-(U_VR5-LX2)") (class "Default")
      (node (ref "U_VR5") (pin "P$2") (pinfunction "LX2_P$2") (pintype "bidirectional"))
      (node (ref "VR5_L1") (pin "1") (pinfunction "1_1") (pintype "passive"))
    )
    (net (code "65") (name "Net-(U_VR5-PS)") (class "Default")
      (node (ref "U_VR5") (pin "P$7") (pinfunction "PS_P$7") (pintype "bidirectional"))
      (node (ref "VR5_0R1") (pin "2") (pinfunction "2_2") (pintype "passive"))
      (node (ref "VR5_0R2") (pin "2") (pinfunction "2_2") (pintype "passive"))
    )
    (net (code "66") (name "VUSB") (class "Default")
      (node (ref "ATMEGA32U4-T") (pin "7") (pinfunction "VBUS_7") (pintype "input"))
      (node (ref "CON_EXTERN") (pin "B_2") (pinfunction "B_2_B_2") (pintype "bidirectional"))
      (node (ref "CON_EXTERN") (pin "T_2") (pinfunction "T_2_T_2") (pintype "bidirectional"))
      (node (ref "LED_CH") (pin "ANODE") (pinfunction "AN_ANODE") (pintype "bidirectional"))
      (node (ref "UC_R6") (pin "2") (pinfunction "2_2") (pintype "passive"))
      (node (ref "U_C3") (pin "1") (pinfunction "1_1") (pintype "passive"))
      (node (ref "U_C4") (pin "1") (pinfunction "1_1") (pintype "passive"))
      (node (ref "U_FB3") (pin "P$2") (pinfunction "P$2_P$2") (pintype "passive"))
      (node (ref "U_MEGA32U-Q") (pin "7") (pinfunction "VBUS_7") (pintype "input"))
      (node (ref "U_USB_CH") (pin "P$2") (pinfunction "ADP_P$2") (pintype "bidirectional"))
      (node (ref "U_USB_CH") (pin "P$6") (pinfunction "EN_P$6") (pintype "bidirectional"))
      (node (ref "U_USB_CH") (pin "P$7") (pinfunction "ENO_P$7") (pintype "bidirectional"))
      (node (ref "U_Z4") (pin "1") (pinfunction "1_1") (pintype "passive"))
    )
    (net (code "67") (name "unconnected-(CON_DUST-NC-PadP$4)") (class "Default")
      (node (ref "CON_DUST") (pin "P$4") (pinfunction "NC_P$4") (pintype "bidirectional"))
    )
    (net (code "68") (name "unconnected-(CON_USB-PadT4)") (class "Default")
      (node (ref "CON_USB") (pin "T4") (pinfunction "T4_T4") (pintype "bidirectional"))
    )
    (net (code "69") (name "unconnected-(U$1-2-AIO2-PadP02)") (class "Default")
      (node (ref "U$1") (pin "P02") (pinfunction "2-AIO2_P02") (pintype "bidirectional"))
    )
    (net (code "70") (name "unconnected-(U$1-3-AIO1-PadP03)") (class "Default")
      (node (ref "U$1") (pin "P03") (pinfunction "3-AIO1_P03") (pintype "bidirectional"))
    )
    (net (code "71") (name "unconnected-(U$1-4-AIO0-PadP04)") (class "Default")
      (node (ref "U$1") (pin "P04") (pinfunction "4-AIO0_P04") (pintype "bidirectional"))
    )
    (net (code "72") (name "unconnected-(U$1-8-CMD-MLDP-PadP08)") (class "Default")
      (node (ref "U$1") (pin "P08") (pinfunction "8-CMD-MLDP_P08") (pintype "bidirectional"))
    )
    (net (code "73") (name "unconnected-(U$1-10-PIO1-SCK-PadP10)") (class "Default")
      (node (ref "U$1") (pin "P10") (pinfunction "10-PIO1-SCK_P10") (pintype "bidirectional"))
    )
    (net (code "74") (name "unconnected-(U$1-11-MLDPEV-PIO2-CS-PadP11)") (class "Default")
      (node (ref "U$1") (pin "P11") (pinfunction "11-MLDPEV-PIO2-CS_P11") (pintype "bidirectional"))
    )
    (net (code "75") (name "unconnected-(U$1-12-WS-PIO3-MOSI-PadP12)") (class "Default")
      (node (ref "U$1") (pin "P12") (pinfunction "12-WS-PIO3-MOSI_P12") (pintype "bidirectional"))
    )
    (net (code "76") (name "unconnected-(U$1-13-PIO4-MISO-PadP13)") (class "Default")
      (node (ref "U$1") (pin "P13") (pinfunction "13-PIO4-MISO_P13") (pintype "bidirectional"))
    )
    (net (code "77") (name "unconnected-(U$1-14-CTS-PIO5-PadP14)") (class "Default")
      (node (ref "U$1") (pin "P14") (pinfunction "14-CTS-PIO5_P14") (pintype "bidirectional"))
    )
    (net (code "78") (name "unconnected-(U$1-17-SPI-{slash}PIO-PadP17)") (class "Default")
      (node (ref "U$1") (pin "P17") (pinfunction "17-SPI-/PIO_P17") (pintype "bidirectional"))
    )
    (net (code "79") (name "unconnected-(U$1-18-RTS-PIO6-PadP18)") (class "Default")
      (node (ref "U$1") (pin "P18") (pinfunction "18-RTS-PIO6_P18") (pintype "bidirectional"))
    )
    (net (code "80") (name "unconnected-(U$1-19-PIO7-PadP19)") (class "Default")
      (node (ref "U$1") (pin "P19") (pinfunction "19-PIO7_P19") (pintype "bidirectional"))
    )
    (net (code "81") (name "unconnected-(U$1-20-RSVD-PadP20)") (class "Default")
      (node (ref "U$1") (pin "P20") (pinfunction "20-RSVD_P20") (pintype "bidirectional"))
    )
    (net (code "82") (name "unconnected-(U$1-21-RSVD-PadP21)") (class "Default")
      (node (ref "U$1") (pin "P21") (pinfunction "21-RSVD_P21") (pintype "bidirectional"))
    )
    (net (code "83") (name "unconnected-(U$1-22-RSVD-PadP22)") (class "Default")
      (node (ref "U$1") (pin "P22") (pinfunction "22-RSVD_P22") (pintype "bidirectional"))
    )
    (net (code "84") (name "unconnected-(U_PUSHB-PadM1)") (class "Default")
      (node (ref "U_PUSHB") (pin "M1") (pinfunction "M1_M1") (pintype "bidirectional"))
    )
    (net (code "85") (name "unconnected-(U_PUSHB-PadM2)") (class "Default")
      (node (ref "U_PUSHB") (pin "M2") (pinfunction "M2_M2") (pintype "bidirectional"))
    )
    (net (code "86") (name "unconnected-(U_PUSHB-PadRS1)") (class "Default")
      (node (ref "U_PUSHB") (pin "RS1") (pinfunction "RS1_RS1") (pintype "bidirectional"))
    )
    (net (code "87") (name "unconnected-(U_PUSHB-PadRS2)") (class "Default")
      (node (ref "U_PUSHB") (pin "RS2") (pinfunction "RS2_RS2") (pintype "bidirectional"))
    )
    (net (code "88") (name "unconnected-(U_TEMP-HUM-PadP$3)") (class "Default")
      (node (ref "U_TEMP-HUM") (pin "P$3") (pinfunction "P$3_P$3") (pintype "bidirectional"))
    )
    (net (code "89") (name "unconnected-(U_USB_CH-CHRADP-PadP$9)") (class "Default")
      (node (ref "U_USB_CH") (pin "P$9") (pinfunction "CHRADP_P$9") (pintype "bidirectional"))
    )
    (net (code "90") (name "unconnected-(U_USB_CH-STAT2_N-PadP$5)") (class "Default")
      (node (ref "U_USB_CH") (pin "P$5") (pinfunction "STAT2_N_P$5") (pintype "bidirectional"))
    )
  )
)
